# ethernet_jack_cnc_shield.net
KiCad netlist of a schematic drawn in EAGLE
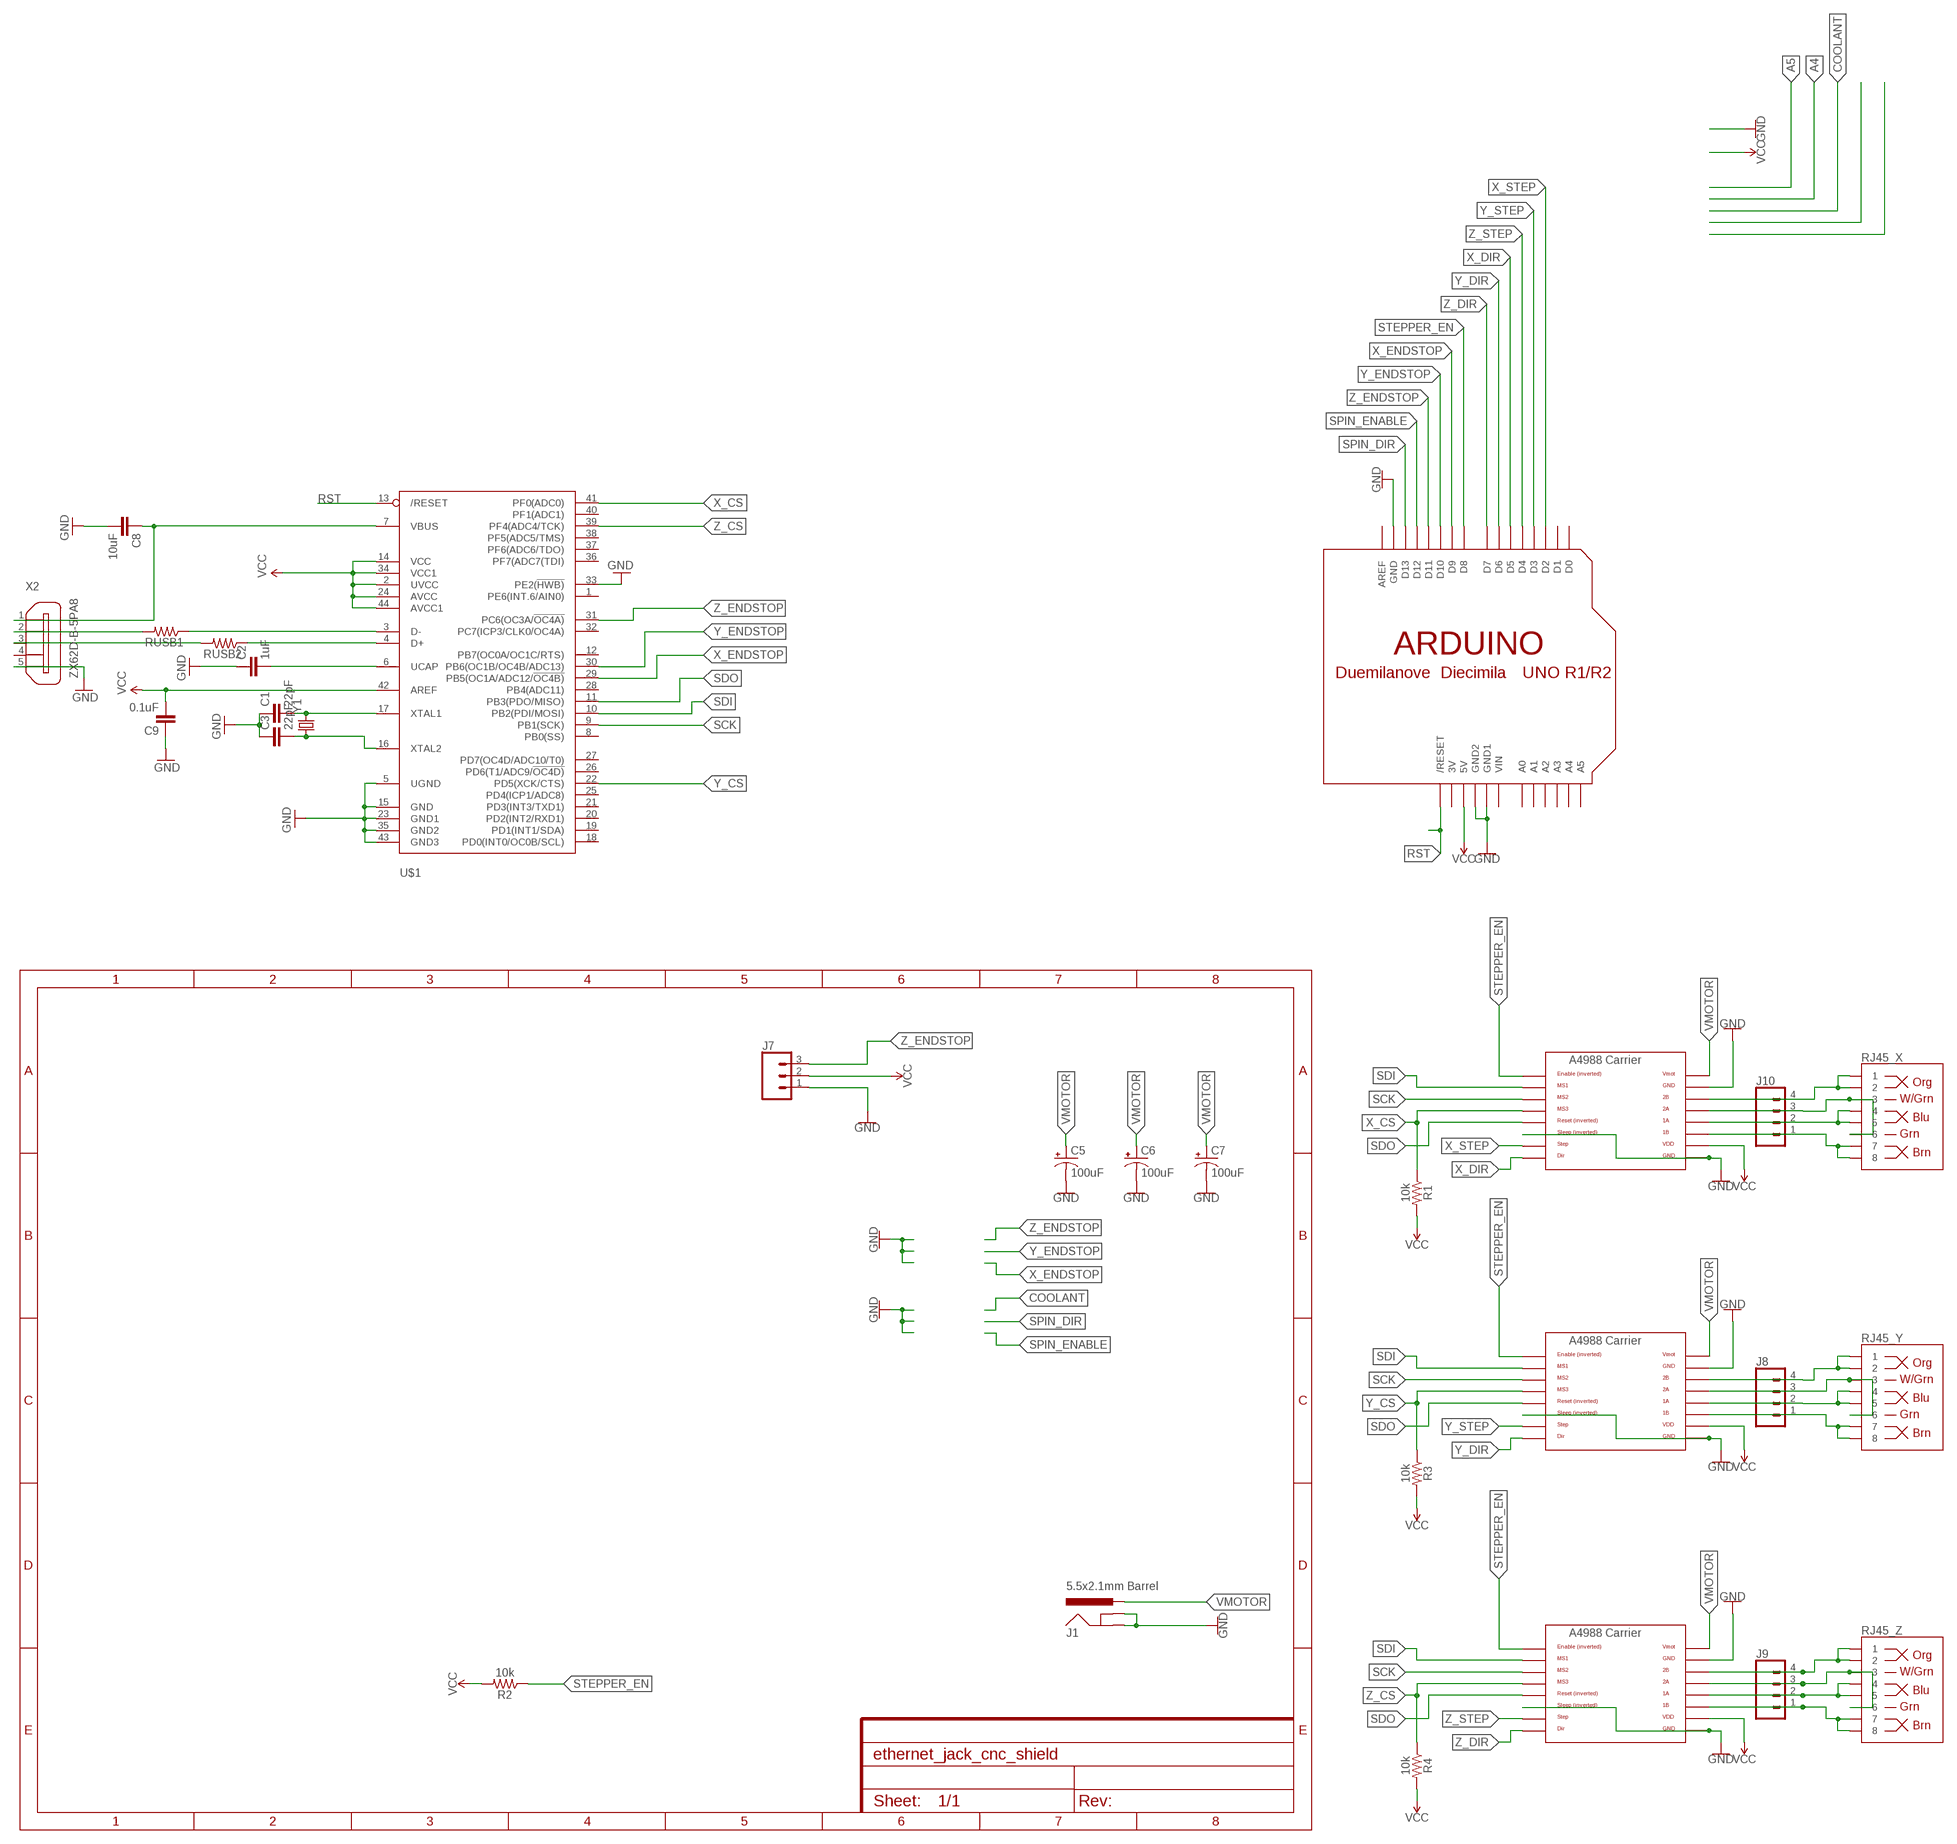
[diagram p0: schematic, sheet 1]

(export (version "E")
  (design (tool "Eeschema 10.0.6"))
  (components
    (comp (ref "C1")
      (value "22pF")
      (footprint "eagle-import:1206")
      (libsource (lib "eagle-import") (part "SparkFun-Passives_CAP1206"))
    )
    (comp (ref "C2")
      (value "1uF")
      (footprint "eagle-import:1206")
      (libsource (lib "eagle-import") (part "CAP1206"))
    )
    (comp (ref "C3")
      (value "22pF")
      (footprint "eagle-import:1206")
      (libsource (lib "eagle-import") (part "SparkFun-Passives_CAP1206"))
    )
    (comp (ref "C5")
      (value "100uF")
      (footprint "eagle-import:PANASONIC_D")
      (libsource (lib "eagle-import") (part "100UF-POLAR-25V-20%(ELEC)"))
    )
    (comp (ref "C6")
      (value "100uF")
      (footprint "eagle-import:PANASONIC_D")
      (libsource (lib "eagle-import") (part "100UF-POLAR-25V-20%(ELEC)"))
    )
    (comp (ref "C7")
      (value "100uF")
      (footprint "eagle-import:PANASONIC_D")
      (libsource (lib "eagle-import") (part "100UF-POLAR-25V-20%(ELEC)"))
    )
    (comp (ref "C8")
      (value "10uF")
      (footprint "eagle-import:1206")
      (libsource (lib "eagle-import") (part "SparkFun-Passives_CAP1206"))
    )
    (comp (ref "C9")
      (value "0.1uF")
      (footprint "eagle-import:1206")
      (libsource (lib "eagle-import") (part "CAP1206"))
    )
    (comp (ref "J1")
      (value "5.5x2.1mm Barrel")
      (footprint "eagle-import:POWER_JACK_SMD")
      (libsource (lib "eagle-import") (part "POWER_JACKSMD"))
    )
    (comp (ref "J7")
      (value "CONN_03")
      (footprint "eagle-import:1X03")
      (libsource (lib "eagle-import") (part "CONN_03"))
    )
    (comp (ref "J8")
      (value "CONN_04")
      (footprint "eagle-import:1X04")
      (libsource (lib "eagle-import") (part "CONN_04"))
    )
    (comp (ref "J9")
      (value "CONN_04")
      (footprint "eagle-import:1X04")
      (libsource (lib "eagle-import") (part "CONN_04"))
    )
    (comp (ref "J10")
      (value "CONN_04")
      (footprint "eagle-import:1X04")
      (libsource (lib "eagle-import") (part "CONN_04"))
    )
    (comp (ref "R1")
      (value "10k")
      (footprint "eagle-import:1206")
      (libsource (lib "eagle-import") (part "SparkFun-Resistors_532_RESISTOR1206"))
    )
    (comp (ref "R2")
      (value "10k")
      (footprint "eagle-import:1206")
      (libsource (lib "eagle-import") (part "SparkFun-Resistors_532_RESISTOR1206"))
    )
    (comp (ref "R3")
      (value "10k")
      (footprint "eagle-import:1206")
      (libsource (lib "eagle-import") (part "SparkFun-Resistors_532_RESISTOR1206"))
    )
    (comp (ref "R4")
      (value "10k")
      (footprint "eagle-import:1206")
      (libsource (lib "eagle-import") (part "SparkFun-Resistors_532_RESISTOR1206"))
    )
    (comp (ref "RJ45_X")
      (value "RJ45")
      (footprint "eagle-import:RJ45-8")
      (libsource (lib "eagle-import") (part "RJ45-8"))
    )
    (comp (ref "RJ45_Y")
      (value "RJ45")
      (footprint "eagle-import:RJ45-8")
      (libsource (lib "eagle-import") (part "RJ45-8"))
    )
    (comp (ref "RJ45_Z")
      (value "RJ45")
      (footprint "eagle-import:RJ45-8")
      (libsource (lib "eagle-import") (part "RJ45-8"))
    )
    (comp (ref "RUSB1")
      (value "RESISTOR1206")
      (footprint "eagle-import:1206")
      (libsource (lib "eagle-import") (part "RESISTOR1206"))
    )
    (comp (ref "RUSB2")
      (value "RESISTOR1206")
      (footprint "eagle-import:1206")
      (libsource (lib "eagle-import") (part "RESISTOR1206"))
    )
    (comp (ref "U$1")
      (value "ATMEGA32U4-AU")
      (footprint "eagle-import:TQFP44")
      (libsource (lib "eagle-import") (part "ATMEGA32U4-AU"))
    )
    (comp (ref "U$2")
      (value "A4988BREAKOUT")
      (footprint "eagle-import:A4988BREAKOUT")
      (libsource (lib "eagle-import") (part "A4988BREAKOUT"))
    )
    (comp (ref "U$3")
      (value "A4988BREAKOUT")
      (footprint "eagle-import:A4988BREAKOUT")
      (libsource (lib "eagle-import") (part "A4988BREAKOUT"))
    )
    (comp (ref "U$4")
      (value "A4988BREAKOUT")
      (footprint "eagle-import:A4988BREAKOUT")
      (libsource (lib "eagle-import") (part "A4988BREAKOUT"))
    )
    (comp (ref "U$6")
      (value "ARDUINOUNO")
      (footprint "eagle-import:ARDUINO")
      (libsource (lib "eagle-import") (part "ARDUINOUNO"))
    )
    (comp (ref "X2")
      (value "ZX62D-B-5PA8")
      (footprint "eagle-import:ZX62D-B-5PA8")
      (fields (field (name "MF") "Hirose"))
      (libsource (lib "eagle-import") (part "ZX62D-B-5PA8"))
    )
    (comp (ref "Y1")
      (value "CRYSTALCRYSTAL-SMD-5X3-16MHZ")
      (footprint "eagle-import:CRYSTAL-SMD-5X3")
      (libsource (lib "eagle-import") (part "CRYSTALCRYSTAL-SMD-5X3-16MHZ"))
    )
  )
  (nets
    (net (code "1") (name "/3V") (class "Default")
      (node (ref "U$6") (pin "3V") (pinfunction "3V_3V") (pintype "power_in"))
    )
    (net (code "2") (name "/VIN") (class "Default")
      (node (ref "U$6") (pin "VIN") (pinfunction "VIN_VIN") (pintype "power_in"))
    )
    (net (code "6") (name "GND") (class "Default")
      (node (ref "C1") (pin "1") (pinfunction "1_1") (pintype "passive"))
      (node (ref "C2") (pin "1") (pinfunction "1_1") (pintype "passive"))
      (node (ref "C3") (pin "1") (pinfunction "1_1") (pintype "passive"))
      (node (ref "C5") (pin "-") (pinfunction "-_-") (pintype "passive"))
      (node (ref "C6") (pin "-") (pinfunction "-_-") (pintype "passive"))
      (node (ref "C7") (pin "-") (pinfunction "-_-") (pintype "passive"))
      (node (ref "C8") (pin "2") (pinfunction "2_2") (pintype "passive"))
      (node (ref "C9") (pin "1") (pinfunction "1_1") (pintype "passive"))
      (node (ref "J1") (pin "GND") (pinfunction "GNDBREAK_GND") (pintype "bidirectional"))
      (node (ref "J1") (pin "P$4") (pinfunction "GND_P$4") (pintype "bidirectional"))
      (node (ref "J7") (pin "1") (pinfunction "1_1") (pintype "passive"))
      (node (ref "U$1") (pin "15") (pinfunction "GND_15") (pintype "bidirectional"))
      (node (ref "U$1") (pin "23") (pinfunction "GND1_23") (pintype "bidirectional"))
      (node (ref "U$1") (pin "33") (pinfunction "PE2(~{HWB})_33") (pintype "bidirectional"))
      (node (ref "U$1") (pin "35") (pinfunction "GND2_35") (pintype "bidirectional"))
      (node (ref "U$1") (pin "43") (pinfunction "GND3_43") (pintype "bidirectional"))
      (node (ref "U$1") (pin "5") (pinfunction "UGND_5") (pintype "bidirectional"))
      (node (ref "U$2") (pin "GND") (pinfunction "GND_GND") (pintype "power_in"))
      (node (ref "U$2") (pin "GND@0") (pinfunction "GND_GND@0") (pintype "power_in"))
      (node (ref "U$2") (pin "SLP") (pinfunction "SLEEP_SLP") (pintype "input"))
      (node (ref "U$3") (pin "GND") (pinfunction "GND_GND") (pintype "power_in"))
      (node (ref "U$3") (pin "GND@0") (pinfunction "GND_GND@0") (pintype "power_in"))
      (node (ref "U$3") (pin "SLP") (pinfunction "SLEEP_SLP") (pintype "input"))
      (node (ref "U$4") (pin "GND") (pinfunction "GND_GND") (pintype "power_in"))
      (node (ref "U$4") (pin "GND@0") (pinfunction "GND_GND@0") (pintype "power_in"))
      (node (ref "U$4") (pin "SLP") (pinfunction "SLEEP_SLP") (pintype "input"))
      (node (ref "U$6") (pin "GND") (pinfunction "GND_GND") (pintype "power_in"))
      (node (ref "U$6") (pin "GND1") (pinfunction "GND1_GND1") (pintype "power_in"))
      (node (ref "U$6") (pin "GND2") (pinfunction "GND2_GND2") (pintype "power_in"))
      (node (ref "X2") (pin "5") (pinfunction "5_5") (pintype "passive"))
    )
    (net (code "7") (name "Net-(J8-Pad1)") (class "Default")
      (node (ref "J8") (pin "1") (pinfunction "1_1") (pintype "passive"))
      (node (ref "RJ45_Y") (pin "7") (pinfunction "7_7") (pintype "bidirectional"))
      (node (ref "RJ45_Y") (pin "8") (pinfunction "8_8") (pintype "bidirectional"))
      (node (ref "U$2") (pin "1B") (pinfunction "1B_1B") (pintype "output"))
    )
    (net (code "8") (name "Net-(J8-Pad2)") (class "Default")
      (node (ref "J8") (pin "2") (pinfunction "2_2") (pintype "passive"))
      (node (ref "RJ45_Y") (pin "4") (pinfunction "4_4") (pintype "bidirectional"))
      (node (ref "RJ45_Y") (pin "5") (pinfunction "5_5") (pintype "bidirectional"))
      (node (ref "U$2") (pin "1A") (pinfunction "1A_1A") (pintype "output"))
    )
    (net (code "9") (name "Net-(J8-Pad3)") (class "Default")
      (node (ref "J8") (pin "3") (pinfunction "3_3") (pintype "passive"))
      (node (ref "RJ45_Y") (pin "3") (pinfunction "3_3") (pintype "bidirectional"))
      (node (ref "RJ45_Y") (pin "6") (pinfunction "6_6") (pintype "bidirectional"))
      (node (ref "U$2") (pin "2A") (pinfunction "2A_2A") (pintype "output"))
    )
    (net (code "10") (name "Net-(J8-Pad4)") (class "Default")
      (node (ref "J8") (pin "4") (pinfunction "4_4") (pintype "passive"))
      (node (ref "RJ45_Y") (pin "1") (pinfunction "1_1") (pintype "bidirectional"))
      (node (ref "RJ45_Y") (pin "2") (pinfunction "2_2") (pintype "bidirectional"))
      (node (ref "U$2") (pin "2B") (pinfunction "2B_2B") (pintype "output"))
    )
    (net (code "11") (name "Net-(J9-Pad1)") (class "Default")
      (node (ref "J9") (pin "1") (pinfunction "1_1") (pintype "passive"))
      (node (ref "RJ45_Z") (pin "7") (pinfunction "7_7") (pintype "bidirectional"))
      (node (ref "RJ45_Z") (pin "8") (pinfunction "8_8") (pintype "bidirectional"))
      (node (ref "U$3") (pin "1B") (pinfunction "1B_1B") (pintype "output"))
    )
    (net (code "12") (name "Net-(J9-Pad2)") (class "Default")
      (node (ref "J9") (pin "2") (pinfunction "2_2") (pintype "passive"))
      (node (ref "RJ45_Z") (pin "4") (pinfunction "4_4") (pintype "bidirectional"))
      (node (ref "RJ45_Z") (pin "5") (pinfunction "5_5") (pintype "bidirectional"))
      (node (ref "U$3") (pin "1A") (pinfunction "1A_1A") (pintype "output"))
    )
    (net (code "13") (name "Net-(J9-Pad3)") (class "Default")
      (node (ref "J9") (pin "3") (pinfunction "3_3") (pintype "passive"))
      (node (ref "RJ45_Z") (pin "3") (pinfunction "3_3") (pintype "bidirectional"))
      (node (ref "RJ45_Z") (pin "6") (pinfunction "6_6") (pintype "bidirectional"))
      (node (ref "U$3") (pin "2A") (pinfunction "2A_2A") (pintype "output"))
    )
    (net (code "14") (name "Net-(J9-Pad4)") (class "Default")
      (node (ref "J9") (pin "4") (pinfunction "4_4") (pintype "passive"))
      (node (ref "RJ45_Z") (pin "1") (pinfunction "1_1") (pintype "bidirectional"))
      (node (ref "RJ45_Z") (pin "2") (pinfunction "2_2") (pintype "bidirectional"))
      (node (ref "U$3") (pin "2B") (pinfunction "2B_2B") (pintype "output"))
    )
    (net (code "15") (name "Net-(J10-Pad1)") (class "Default")
      (node (ref "J10") (pin "1") (pinfunction "1_1") (pintype "passive"))
      (node (ref "RJ45_X") (pin "7") (pinfunction "7_7") (pintype "bidirectional"))
      (node (ref "RJ45_X") (pin "8") (pinfunction "8_8") (pintype "bidirectional"))
      (node (ref "U$4") (pin "1B") (pinfunction "1B_1B") (pintype "output"))
    )
    (net (code "16") (name "Net-(J10-Pad2)") (class "Default")
      (node (ref "J10") (pin "2") (pinfunction "2_2") (pintype "passive"))
      (node (ref "RJ45_X") (pin "4") (pinfunction "4_4") (pintype "bidirectional"))
      (node (ref "RJ45_X") (pin "5") (pinfunction "5_5") (pintype "bidirectional"))
      (node (ref "U$4") (pin "1A") (pinfunction "1A_1A") (pintype "output"))
    )
    (net (code "17") (name "Net-(J10-Pad3)") (class "Default")
      (node (ref "J10") (pin "3") (pinfunction "3_3") (pintype "passive"))
      (node (ref "RJ45_X") (pin "3") (pinfunction "3_3") (pintype "bidirectional"))
      (node (ref "RJ45_X") (pin "6") (pinfunction "6_6") (pintype "bidirectional"))
      (node (ref "U$4") (pin "2A") (pinfunction "2A_2A") (pintype "output"))
    )
    (net (code "18") (name "Net-(J10-Pad4)") (class "Default")
      (node (ref "J10") (pin "4") (pinfunction "4_4") (pintype "passive"))
      (node (ref "RJ45_X") (pin "1") (pinfunction "1_1") (pintype "bidirectional"))
      (node (ref "RJ45_X") (pin "2") (pinfunction "2_2") (pintype "bidirectional"))
      (node (ref "U$4") (pin "2B") (pinfunction "2B_2B") (pintype "output"))
    )
    (net (code "19") (name "Net-(RUSB1-Pad2)") (class "Default")
      (node (ref "RUSB1") (pin "2") (pinfunction "2_2") (pintype "passive"))
      (node (ref "X2") (pin "2") (pinfunction "2_2") (pintype "passive"))
    )
    (net (code "20") (name "Net-(RUSB2-Pad2)") (class "Default")
      (node (ref "RUSB2") (pin "2") (pinfunction "2_2") (pintype "passive"))
      (node (ref "X2") (pin "3") (pinfunction "3_3") (pintype "passive"))
    )
    (net (code "21") (name "Net-(U$1-D+)") (class "Default")
      (node (ref "RUSB2") (pin "1") (pinfunction "1_1") (pintype "passive"))
      (node (ref "U$1") (pin "4") (pinfunction "D+_4") (pintype "bidirectional"))
    )
    (net (code "22") (name "Net-(U$1-D-)") (class "Default")
      (node (ref "RUSB1") (pin "1") (pinfunction "1_1") (pintype "passive"))
      (node (ref "U$1") (pin "3") (pinfunction "D-_3") (pintype "bidirectional"))
    )
    (net (code "23") (name "Net-(U$1-UCAP)") (class "Default")
      (node (ref "C2") (pin "2") (pinfunction "2_2") (pintype "passive"))
      (node (ref "U$1") (pin "6") (pinfunction "UCAP_6") (pintype "bidirectional"))
    )
    (net (code "24") (name "Net-(U$1-VBUS)") (class "Default")
      (node (ref "C8") (pin "1") (pinfunction "1_1") (pintype "passive"))
      (node (ref "U$1") (pin "7") (pinfunction "VBUS_7") (pintype "bidirectional"))
      (node (ref "X2") (pin "1") (pinfunction "1_1") (pintype "passive"))
    )
    (net (code "25") (name "Net-(U$1-XTAL1)") (class "Default")
      (node (ref "C1") (pin "2") (pinfunction "2_2") (pintype "passive"))
      (node (ref "U$1") (pin "17") (pinfunction "XTAL1_17") (pintype "bidirectional"))
      (node (ref "Y1") (pin "3") (pinfunction "2_3") (pintype "passive"))
    )
    (net (code "26") (name "Net-(U$1-XTAL2)") (class "Default")
      (node (ref "C3") (pin "2") (pinfunction "2_2") (pintype "passive"))
      (node (ref "U$1") (pin "16") (pinfunction "XTAL2_16") (pintype "bidirectional"))
      (node (ref "Y1") (pin "1") (pinfunction "1_1") (pintype "passive"))
    )
    (net (code "27") (name "RST") (class "Default")
      (node (ref "U$1") (pin "13") (pinfunction "/RESET_13") (pintype "bidirectional"))
      (node (ref "U$6") (pin "RESET") (pinfunction "/RESET_RESET") (pintype "bidirectional"))
    )
    (net (code "28") (name "SCK") (class "Default")
      (node (ref "U$1") (pin "9") (pinfunction "PB1(SCK)_9") (pintype "bidirectional"))
      (node (ref "U$2") (pin "MS2") (pinfunction "MS2_MS2") (pintype "input"))
      (node (ref "U$3") (pin "MS2") (pinfunction "MS2_MS2") (pintype "input"))
      (node (ref "U$4") (pin "MS2") (pinfunction "MS2_MS2") (pintype "input"))
    )
    (net (code "29") (name "SDI") (class "Default")
      (node (ref "U$1") (pin "10") (pinfunction "PB2(PDI/MOSI)_10") (pintype "bidirectional"))
      (node (ref "U$2") (pin "MS1") (pinfunction "MS1_MS1") (pintype "input"))
      (node (ref "U$3") (pin "MS1") (pinfunction "MS1_MS1") (pintype "input"))
      (node (ref "U$4") (pin "MS1") (pinfunction "MS1_MS1") (pintype "input"))
    )
    (net (code "30") (name "SDO") (class "Default")
      (node (ref "U$1") (pin "11") (pinfunction "PB3(PDO/MISO)_11") (pintype "bidirectional"))
      (node (ref "U$2") (pin "RST") (pinfunction "RST_RST") (pintype "input"))
      (node (ref "U$3") (pin "RST") (pinfunction "RST_RST") (pintype "input"))
      (node (ref "U$4") (pin "RST") (pinfunction "RST_RST") (pintype "input"))
    )
    (net (code "31") (name "SPIN_DIR") (class "Default")
      (node (ref "U$6") (pin "D13") (pinfunction "D13_D13") (pintype "bidirectional"))
    )
    (net (code "32") (name "SPIN_ENABLE") (class "Default")
      (node (ref "U$6") (pin "D12") (pinfunction "D12_D12") (pintype "bidirectional"))
    )
    (net (code "33") (name "STEPPER_EN") (class "Default")
      (node (ref "R2") (pin "1") (pinfunction "1_1") (pintype "passive"))
      (node (ref "U$2") (pin "EN") (pinfunction "EN_EN") (pintype "input"))
      (node (ref "U$3") (pin "EN") (pinfunction "EN_EN") (pintype "input"))
      (node (ref "U$4") (pin "EN") (pinfunction "EN_EN") (pintype "input"))
      (node (ref "U$6") (pin "D8") (pinfunction "D8_D8") (pintype "bidirectional"))
    )
    (net (code "34") (name "VCC") (class "Default")
      (node (ref "C9") (pin "2") (pinfunction "2_2") (pintype "passive"))
      (node (ref "J7") (pin "2") (pinfunction "2_2") (pintype "passive"))
      (node (ref "R1") (pin "2") (pinfunction "2_2") (pintype "passive"))
      (node (ref "R2") (pin "2") (pinfunction "2_2") (pintype "passive"))
      (node (ref "R3") (pin "2") (pinfunction "2_2") (pintype "passive"))
      (node (ref "R4") (pin "2") (pinfunction "2_2") (pintype "passive"))
      (node (ref "U$1") (pin "14") (pinfunction "VCC_14") (pintype "bidirectional"))
      (node (ref "U$1") (pin "2") (pinfunction "UVCC_2") (pintype "bidirectional"))
      (node (ref "U$1") (pin "24") (pinfunction "AVCC_24") (pintype "bidirectional"))
      (node (ref "U$1") (pin "34") (pinfunction "VCC1_34") (pintype "bidirectional"))
      (node (ref "U$1") (pin "42") (pinfunction "AREF_42") (pintype "bidirectional"))
      (node (ref "U$1") (pin "44") (pinfunction "AVCC1_44") (pintype "bidirectional"))
      (node (ref "U$2") (pin "VDD") (pinfunction "VDD_VDD") (pintype "power_in"))
      (node (ref "U$3") (pin "VDD") (pinfunction "VDD_VDD") (pintype "power_in"))
      (node (ref "U$4") (pin "VDD") (pinfunction "VDD_VDD") (pintype "power_in"))
      (node (ref "U$6") (pin "5V") (pinfunction "5V_5V") (pintype "power_in"))
    )
    (net (code "35") (name "VMOTOR") (class "Default")
      (node (ref "C5") (pin "+") (pinfunction "+_+") (pintype "passive"))
      (node (ref "C6") (pin "+") (pinfunction "+_+") (pintype "passive"))
      (node (ref "C7") (pin "+") (pinfunction "+_+") (pintype "passive"))
      (node (ref "J1") (pin "VIN0") (pinfunction "PWR_VIN0") (pintype "bidirectional"))
      (node (ref "U$2") (pin "VMOT") (pinfunction "VMOT_VMOT") (pintype "power_in"))
      (node (ref "U$3") (pin "VMOT") (pinfunction "VMOT_VMOT") (pintype "power_in"))
      (node (ref "U$4") (pin "VMOT") (pinfunction "VMOT_VMOT") (pintype "power_in"))
    )
    (net (code "36") (name "X_CS") (class "Default")
      (node (ref "R1") (pin "1") (pinfunction "1_1") (pintype "passive"))
      (node (ref "U$1") (pin "41") (pinfunction "PF0(ADC0)_41") (pintype "bidirectional"))
      (node (ref "U$4") (pin "MS3") (pinfunction "MS3_MS3") (pintype "input"))
    )
    (net (code "37") (name "X_DIR") (class "Default")
      (node (ref "U$4") (pin "DIR") (pinfunction "DIR_DIR") (pintype "input"))
      (node (ref "U$6") (pin "D5") (pinfunction "D5_D5") (pintype "bidirectional"))
    )
    (net (code "38") (name "X_ENDSTOP") (class "Default")
      (node (ref "U$1") (pin "29") (pinfunction "PB5(OC1A/ADC12/~{OC4B})_29") (pintype "bidirectional"))
      (node (ref "U$6") (pin "D9") (pinfunction "D9_D9") (pintype "bidirectional"))
    )
    (net (code "39") (name "X_STEP") (class "Default")
      (node (ref "U$4") (pin "STEP") (pinfunction "STEP_STEP") (pintype "input"))
      (node (ref "U$6") (pin "D2") (pinfunction "D2_D2") (pintype "bidirectional"))
    )
    (net (code "40") (name "Y_CS") (class "Default")
      (node (ref "R3") (pin "1") (pinfunction "1_1") (pintype "passive"))
      (node (ref "U$1") (pin "22") (pinfunction "PD5(XCK/CTS)_22") (pintype "bidirectional"))
      (node (ref "U$2") (pin "MS3") (pinfunction "MS3_MS3") (pintype "input"))
    )
    (net (code "41") (name "Y_DIR") (class "Default")
      (node (ref "U$2") (pin "DIR") (pinfunction "DIR_DIR") (pintype "input"))
      (node (ref "U$6") (pin "D6") (pinfunction "D6_D6") (pintype "bidirectional"))
    )
    (net (code "42") (name "Y_ENDSTOP") (class "Default")
      (node (ref "U$1") (pin "30") (pinfunction "PB6(OC1B/OC4B/ADC13)_30") (pintype "bidirectional"))
      (node (ref "U$6") (pin "D10") (pinfunction "D10_D10") (pintype "bidirectional"))
    )
    (net (code "43") (name "Y_STEP") (class "Default")
      (node (ref "U$2") (pin "STEP") (pinfunction "STEP_STEP") (pintype "input"))
      (node (ref "U$6") (pin "D3") (pinfunction "D3_D3") (pintype "bidirectional"))
    )
    (net (code "44") (name "Z_CS") (class "Default")
      (node (ref "R4") (pin "1") (pinfunction "1_1") (pintype "passive"))
      (node (ref "U$1") (pin "39") (pinfunction "PF4(ADC4/TCK)_39") (pintype "bidirectional"))
      (node (ref "U$3") (pin "MS3") (pinfunction "MS3_MS3") (pintype "input"))
    )
    (net (code "45") (name "Z_DIR") (class "Default")
      (node (ref "U$3") (pin "DIR") (pinfunction "DIR_DIR") (pintype "input"))
      (node (ref "U$6") (pin "D7") (pinfunction "D7_D7") (pintype "bidirectional"))
    )
    (net (code "46") (name "Z_ENDSTOP") (class "Default")
      (node (ref "J7") (pin "3") (pinfunction "3_3") (pintype "passive"))
      (node (ref "U$1") (pin "31") (pinfunction "PC6(OC3A/~{OC4A})_31") (pintype "bidirectional"))
      (node (ref "U$6") (pin "D11") (pinfunction "D11_D11") (pintype "bidirectional"))
    )
    (net (code "47") (name "Z_STEP") (class "Default")
      (node (ref "U$3") (pin "STEP") (pinfunction "STEP_STEP") (pintype "input"))
      (node (ref "U$6") (pin "D4") (pinfunction "D4_D4") (pintype "bidirectional"))
    )
    (net (code "48") (name "unconnected-(U$1-PB0(SS)-Pad8)") (class "Default")
      (node (ref "U$1") (pin "8") (pinfunction "PB0(SS)_8") (pintype "bidirectional"))
    )
    (net (code "49") (name "unconnected-(U$1-PB4(ADC11)-Pad28)") (class "Default")
      (node (ref "U$1") (pin "28") (pinfunction "PB4(ADC11)_28") (pintype "bidirectional"))
    )
    (net (code "50") (name "unconnected-(U$1-PB7(OC0A{slash}OC1C{slash}RTS)-Pad12)") (class "Default")
      (node (ref "U$1") (pin "12") (pinfunction "PB7(OC0A/OC1C/RTS)_12") (pintype "bidirectional"))
    )
    (net (code "51") (name "unconnected-(U$1-PC7(ICP3{slash}CLK0{slash}OC4A)-Pad32)") (class "Default")
      (node (ref "U$1") (pin "32") (pinfunction "PC7(ICP3/CLK0/OC4A)_32") (pintype "bidirectional"))
    )
    (net (code "52") (name "unconnected-(U$1-PD0(INT0{slash}OC0B{slash}SCL)-Pad18)") (class "Default")
      (node (ref "U$1") (pin "18") (pinfunction "PD0(INT0/OC0B/SCL)_18") (pintype "bidirectional"))
    )
    (net (code "53") (name "unconnected-(U$1-PD1(INT1{slash}SDA)-Pad19)") (class "Default")
      (node (ref "U$1") (pin "19") (pinfunction "PD1(INT1/SDA)_19") (pintype "bidirectional"))
    )
    (net (code "54") (name "unconnected-(U$1-PD2(INT2{slash}RXD1)-Pad20)") (class "Default")
      (node (ref "U$1") (pin "20") (pinfunction "PD2(INT2/RXD1)_20") (pintype "bidirectional"))
    )
    (net (code "55") (name "unconnected-(U$1-PD3(INT3{slash}TXD1)-Pad21)") (class "Default")
      (node (ref "U$1") (pin "21") (pinfunction "PD3(INT3/TXD1)_21") (pintype "bidirectional"))
    )
    (net (code "56") (name "unconnected-(U$1-PD4(ICP1{slash}ADC8)-Pad25)") (class "Default")
      (node (ref "U$1") (pin "25") (pinfunction "PD4(ICP1/ADC8)_25") (pintype "bidirectional"))
    )
    (net (code "57") (name "unconnected-(U$1-PD6(T1{slash}ADC9{slash}~{OC4D})-Pad26)") (class "Default")
      (node (ref "U$1") (pin "26") (pinfunction "PD6(T1/ADC9/~{OC4D})_26") (pintype "bidirectional"))
    )
    (net (code "58") (name "unconnected-(U$1-PD7(OC4D{slash}ADC10{slash}T0)-Pad27)") (class "Default")
      (node (ref "U$1") (pin "27") (pinfunction "PD7(OC4D/ADC10/T0)_27") (pintype "bidirectional"))
    )
    (net (code "59") (name "unconnected-(U$1-PE6(INT.6{slash}AIN0)-Pad1)") (class "Default")
      (node (ref "U$1") (pin "1") (pinfunction "PE6(INT.6/AIN0)_1") (pintype "bidirectional"))
    )
    (net (code "60") (name "unconnected-(U$1-PF1(ADC1)-Pad40)") (class "Default")
      (node (ref "U$1") (pin "40") (pinfunction "PF1(ADC1)_40") (pintype "bidirectional"))
    )
    (net (code "61") (name "unconnected-(U$1-PF5(ADC5{slash}TMS)-Pad38)") (class "Default")
      (node (ref "U$1") (pin "38") (pinfunction "PF5(ADC5/TMS)_38") (pintype "bidirectional"))
    )
    (net (code "62") (name "unconnected-(U$1-PF6(ADC6{slash}TDO)-Pad37)") (class "Default")
      (node (ref "U$1") (pin "37") (pinfunction "PF6(ADC6/TDO)_37") (pintype "bidirectional"))
    )
    (net (code "63") (name "unconnected-(U$1-PF7(ADC7(TDI)-Pad36)") (class "Default")
      (node (ref "U$1") (pin "36") (pinfunction "PF7(ADC7(TDI)_36") (pintype "bidirectional"))
    )
    (net (code "64") (name "unconnected-(U$6-PadA0)") (class "Default")
      (node (ref "U$6") (pin "A0") (pinfunction "A0_A0") (pintype "bidirectional"))
    )
    (net (code "65") (name "unconnected-(U$6-PadA1)") (class "Default")
      (node (ref "U$6") (pin "A1") (pinfunction "A1_A1") (pintype "bidirectional"))
    )
    (net (code "66") (name "unconnected-(U$6-PadA2)") (class "Default")
      (node (ref "U$6") (pin "A2") (pinfunction "A2_A2") (pintype "bidirectional"))
    )
    (net (code "67") (name "unconnected-(U$6-PadA3)") (class "Default")
      (node (ref "U$6") (pin "A3") (pinfunction "A3_A3") (pintype "bidirectional"))
    )
    (net (code "68") (name "unconnected-(U$6-PadA4)") (class "Default")
      (node (ref "U$6") (pin "A4") (pinfunction "A4_A4") (pintype "bidirectional"))
    )
    (net (code "69") (name "unconnected-(U$6-PadA5)") (class "Default")
      (node (ref "U$6") (pin "A5") (pinfunction "A5_A5") (pintype "bidirectional"))
    )
    (net (code "70") (name "unconnected-(U$6-PadAREF)") (class "Default")
      (node (ref "U$6") (pin "AREF") (pinfunction "AREF_AREF") (pintype "bidirectional"))
    )
    (net (code "71") (name "unconnected-(U$6-PadD0)") (class "Default")
      (node (ref "U$6") (pin "D0") (pinfunction "D0_D0") (pintype "bidirectional"))
    )
    (net (code "72") (name "unconnected-(U$6-PadD1)") (class "Default")
      (node (ref "U$6") (pin "D1") (pinfunction "D1_D1") (pintype "bidirectional"))
    )
    (net (code "73") (name "unconnected-(X2-Pad4)") (class "Default")
      (node (ref "X2") (pin "4") (pinfunction "4_4") (pintype "passive"))
    )
  )
)
